# 03_-_MAIN_BOARD.net
KiCad netlist of a schematic drawn in Altium Designer
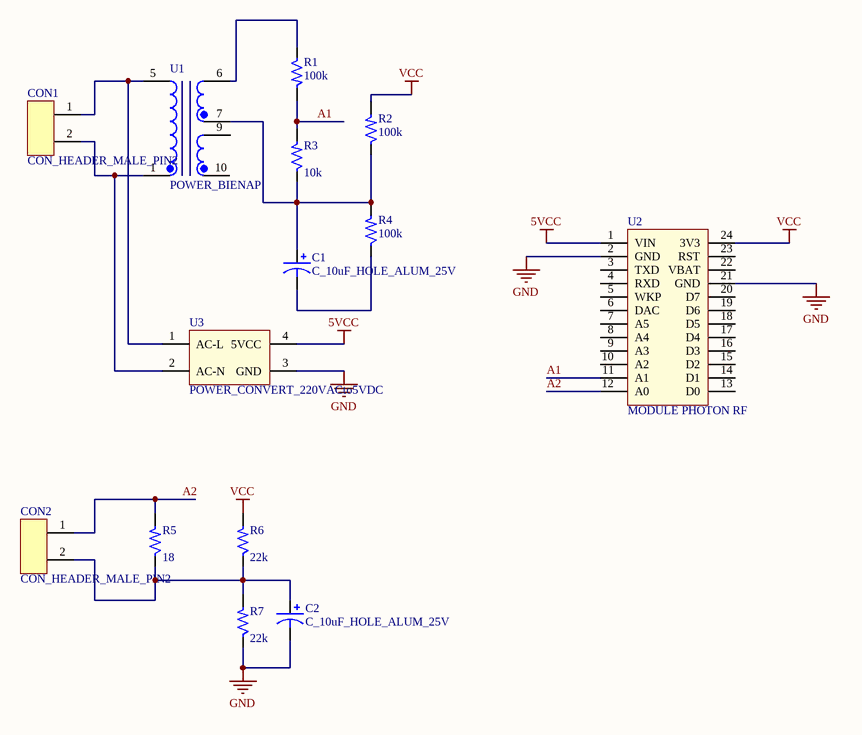
[diagram p0: [03] - MAIN BOARD.SchDoc]

(export (version "E")
  (design (tool "Eeschema 10.0.6"))
  (components
    (comp (ref "C1")
      (value "C_10uF_HOLE_ALUM_25V")
      (footprint "C_10uF_HOLE_5mm")
      (description "CAP ALUM 10uF 20% 25V")
      (fields
        (field (name "MANUFACTURER") "Panasonic Electronic Components")
        (field (name "MANUFACTURER PART NUMBER") "ECE-A1EN100U")
      )
      (libsource (lib "SchematicLib") (part "C_10uF_HOLE_ALUM_25V"))
    )
    (comp (ref "C2")
      (value "C_10uF_HOLE_ALUM_25V")
      (footprint "C_10uF_HOLE_5mm")
      (description "CAP ALUM 10uF 20% 25V")
      (fields
        (field (name "MANUFACTURER") "Panasonic Electronic Components")
        (field (name "MANUFACTURER PART NUMBER") "ECE-A1EN100U")
      )
      (libsource (lib "SchematicLib") (part "C_10uF_HOLE_ALUM_25V"))
    )
    (comp (ref "CON1")
      (value "CON_HEADER_MALE_PIN2")
      (footprint "CON_HEADER_MALE_VAC")
      (description "TERM BLOCK HDR 2POS R/A 5.08MM")
      (fields
        (field (name "MANUFACTURER") "TE Connectivity AMP Connectors")
        (field (name "MANUFACTURER PART NUMBER") "282815-2")
      )
      (libsource (lib "SchematicLib") (part "CON_HEADER_MALE_PIN2"))
    )
    (comp (ref "CON2")
      (value "CON_HEADER_MALE_PIN2")
      (footprint "CON_HEADER_MALE_PIN2")
      (description "TERM BLOCK HDR 2POS R/A 5.08MM")
      (fields
        (field (name "MANUFACTURER") "TE Connectivity AMP Connectors")
        (field (name "MANUFACTURER PART NUMBER") "282815-2")
      )
      (libsource (lib "SchematicLib") (part "CON_HEADER_MALE_PIN2"))
    )
    (comp (ref "R1")
      (value "R_100k_HOLE_0.1%_1W")
      (footprint "R_HOLE_0.25W_0.4")
      (description "RESISTOR METAL FILM 1W 100K OHM")
      (fields
        (field (name "MANUFACTURER") "Vishay Dale")
        (field (name "MANUFACTURER PART NUMBER") "CPF1100K00BHEE6")
        (field (name "RESISTANCE (OHMS)") "100k")
      )
      (libsource (lib "ALTIUM_LIB") (part "R_100k_HOLE_0.1%_1W"))
    )
    (comp (ref "R2")
      (value "R_100k_HOLE_0.1%_1W")
      (footprint "R_HOLE_0.25W_0.4")
      (description "RESISTOR METAL FILM 1W 100K OHM")
      (fields
        (field (name "MANUFACTURER") "Vishay Dale")
        (field (name "MANUFACTURER PART NUMBER") "CPF1100K00BHEE6")
        (field (name "RESISTANCE (OHMS)") "100k")
      )
      (libsource (lib "ALTIUM_LIB") (part "R_100k_HOLE_0.1%_1W"))
    )
    (comp (ref "R3")
      (value "R_10K_HOLE_1%_1W")
      (footprint "R_HOLE_0.25W_0.4")
      (description "RES 10.0K OHM 1W 1% AXIAL")
      (fields
        (field (name "MANUFACTURER") "Vishay Dale")
        (field (name "MANUFACTURER PART NUMBER") "CMF6010K000FKEB")
        (field (name "RESISTANCE (OHMS)") "10k")
      )
      (libsource (lib "ALTIUM_LIB") (part "R_10K_HOLE_1%_1W"))
    )
    (comp (ref "R4")
      (value "R_100k_HOLE_0.1%_1W")
      (footprint "R_HOLE_0.25W_0.4")
      (description "RESISTOR METAL FILM 1W 100K OHM")
      (fields
        (field (name "MANUFACTURER") "Vishay Dale")
        (field (name "MANUFACTURER PART NUMBER") "CPF1100K00BHEE6")
        (field (name "RESISTANCE (OHMS)") "100k")
      )
      (libsource (lib "ALTIUM_LIB") (part "R_100k_HOLE_0.1%_1W"))
    )
    (comp (ref "R5")
      (value "R_18_HOLE_1%_1W")
      (footprint "R_HOLE_0.25W_0.4")
      (description "RES 18 OHM 1W 1% AXIAL")
      (fields
        (field (name "MANUFACTURER") "Vishay Dale")
        (field (name "MANUFACTURER PART NUMBER") "ALSR0118R00FE12")
        (field (name "RESISTANCE (OHMS)") "18")
      )
      (libsource (lib "ALTIUM_LIB") (part "R_18_HOLE_1%_1W"))
    )
    (comp (ref "R6")
      (value "R_22K_HOLE_1%_1/4W")
      (footprint "R_HOLE_0.25W_0.4")
      (description "RES 22K OHM 1/4W 1% AXIAL")
      (fields
        (field (name "MANUFACTURER") "Stackpole Electronics Inc.")
        (field (name "MANUFACTURER PART NUMBER") "RNMF14FTC22K0")
        (field (name "RESISTANCE (OHMS)") "22k")
      )
      (libsource (lib "ALTIUM_LIB") (part "R_22K_HOLE_1%_1/4W"))
    )
    (comp (ref "R7")
      (value "R_22K_HOLE_1%_1/4W")
      (footprint "R_HOLE_0.25W_0.4")
      (description "RES 22K OHM 1/4W 1% AXIAL")
      (fields
        (field (name "MANUFACTURER") "Stackpole Electronics Inc.")
        (field (name "MANUFACTURER PART NUMBER") "RNMF14FTC22K0")
        (field (name "RESISTANCE (OHMS)") "22k")
      )
      (libsource (lib "ALTIUM_LIB") (part "R_22K_HOLE_1%_1/4W"))
    )
    (comp (ref "U1")
      (value "POWER_BIENAP")
      (footprint "POWER_BIEN_AP")
      (libsource (lib "ALTIUM_LIB") (part "POWER_BIENAP"))
    )
    (comp (ref "U2")
      (value "MODULE PHOTON RF")
      (footprint "MODULE PHOTON RF")
      (description "PARTICLE PHOTON")
      (fields
        (field (name "MANUFACTURER") "Seeed Technology Co., Ltd")
        (field (name "MANUFACTURER PART NUMBER") "114990286")
      )
      (libsource (lib "ALTIUM_LIB") (part "MODULE PHOTON RF"))
    )
    (comp (ref "U3")
      (value "POWER_CONVERT_220VACto5VDC")
      (footprint "POWER_CONVERT220VACto5VDC")
      (libsource (lib "SchematicLib") (part "POWER_CONVERT_220VACto5VDC"))
    )
  )
  (nets
    (net (code "1") (name "/A1") (class "Default")
      (node (ref "R1") (pin "2") (pinfunction "2_2") (pintype "passive"))
      (node (ref "R3") (pin "2") (pinfunction "2_2") (pintype "passive"))
      (node (ref "U2") (pin "11") (pinfunction "A1_11") (pintype "passive"))
    )
    (net (code "2") (name "/A2") (class "Default")
      (node (ref "CON2") (pin "1") (pinfunction "SIGN+_1") (pintype "passive"))
      (node (ref "R5") (pin "2") (pinfunction "2_2") (pintype "passive"))
      (node (ref "U2") (pin "12") (pinfunction "A0_12") (pintype "passive"))
    )
    (net (code "3") (name "5VCC") (class "Default")
      (node (ref "U2") (pin "1") (pinfunction "VIN_1") (pintype "passive"))
      (node (ref "U3") (pin "4") (pinfunction "5VCC_4") (pintype "passive"))
    )
    (net (code "4") (name "GND") (class "Default")
      (node (ref "C2") (pin "2") (pinfunction "2_2") (pintype "passive"))
      (node (ref "R7") (pin "1") (pinfunction "1_1") (pintype "passive"))
      (node (ref "U2") (pin "2") (pinfunction "GND_2") (pintype "passive"))
      (node (ref "U2") (pin "21") (pinfunction "GND_21") (pintype "passive"))
      (node (ref "U3") (pin "3") (pinfunction "GND_3") (pintype "passive"))
    )
    (net (code "5") (name "Net-(C1-Pad1)") (class "Default")
      (node (ref "C1") (pin "1") (pinfunction "1_1") (pintype "passive"))
      (node (ref "R2") (pin "1") (pinfunction "1_1") (pintype "passive"))
      (node (ref "R3") (pin "1") (pinfunction "1_1") (pintype "passive"))
      (node (ref "R4") (pin "2") (pinfunction "2_2") (pintype "passive"))
      (node (ref "U1") (pin "7") (pinfunction "7_7") (pintype "passive"))
    )
    (net (code "6") (name "Net-(C1-Pad2)") (class "Default")
      (node (ref "C1") (pin "2") (pinfunction "2_2") (pintype "passive"))
      (node (ref "R4") (pin "1") (pinfunction "1_1") (pintype "passive"))
    )
    (net (code "7") (name "Net-(CON1-SIGN+)") (class "Default")
      (node (ref "CON1") (pin "1") (pinfunction "SIGN+_1") (pintype "passive"))
      (node (ref "U1") (pin "5") (pinfunction "5_5") (pintype "passive"))
      (node (ref "U3") (pin "1") (pinfunction "AC-L_1") (pintype "passive"))
    )
    (net (code "8") (name "Net-(CON1-SIGN-)") (class "Default")
      (node (ref "CON1") (pin "2") (pinfunction "SIGN-_2") (pintype "passive"))
      (node (ref "U1") (pin "1") (pinfunction "1_1") (pintype "passive"))
      (node (ref "U3") (pin "2") (pinfunction "AC-N_2") (pintype "passive"))
    )
    (net (code "9") (name "Net-(CON2-SIGN-)") (class "Default")
      (node (ref "C2") (pin "1") (pinfunction "1_1") (pintype "passive"))
      (node (ref "CON2") (pin "2") (pinfunction "SIGN-_2") (pintype "passive"))
      (node (ref "R5") (pin "1") (pinfunction "1_1") (pintype "passive"))
      (node (ref "R6") (pin "1") (pinfunction "1_1") (pintype "passive"))
      (node (ref "R7") (pin "2") (pinfunction "2_2") (pintype "passive"))
    )
    (net (code "10") (name "Net-(R1-Pad1)") (class "Default")
      (node (ref "R1") (pin "1") (pinfunction "1_1") (pintype "passive"))
      (node (ref "U1") (pin "6") (pinfunction "6_6") (pintype "passive"))
    )
    (net (code "11") (name "VCC") (class "Default")
      (node (ref "R2") (pin "2") (pinfunction "2_2") (pintype "passive"))
      (node (ref "R6") (pin "2") (pinfunction "2_2") (pintype "passive"))
      (node (ref "U2") (pin "24") (pinfunction "3V3_24") (pintype "passive"))
    )
    (net (code "12") (name "unconnected-(U1-Pad9)") (class "Default")
      (node (ref "U1") (pin "9") (pinfunction "9_9") (pintype "passive"))
    )
    (net (code "13") (name "unconnected-(U1-Pad10)") (class "Default")
      (node (ref "U1") (pin "10") (pinfunction "10_10") (pintype "passive"))
    )
    (net (code "14") (name "unconnected-(U2-A2-Pad10)") (class "Default")
      (node (ref "U2") (pin "10") (pinfunction "A2_10") (pintype "passive"))
    )
    (net (code "15") (name "unconnected-(U2-A3-Pad9)") (class "Default")
      (node (ref "U2") (pin "9") (pinfunction "A3_9") (pintype "passive"))
    )
    (net (code "16") (name "unconnected-(U2-A4-Pad8)") (class "Default")
      (node (ref "U2") (pin "8") (pinfunction "A4_8") (pintype "passive"))
    )
    (net (code "17") (name "unconnected-(U2-A5-Pad7)") (class "Default")
      (node (ref "U2") (pin "7") (pinfunction "A5_7") (pintype "passive"))
    )
    (net (code "18") (name "unconnected-(U2-D0-Pad13)") (class "Default")
      (node (ref "U2") (pin "13") (pinfunction "D0_13") (pintype "passive"))
    )
    (net (code "19") (name "unconnected-(U2-D1-Pad14)") (class "Default")
      (node (ref "U2") (pin "14") (pinfunction "D1_14") (pintype "passive"))
    )
    (net (code "20") (name "unconnected-(U2-D2-Pad15)") (class "Default")
      (node (ref "U2") (pin "15") (pinfunction "D2_15") (pintype "passive"))
    )
    (net (code "21") (name "unconnected-(U2-D3-Pad16)") (class "Default")
      (node (ref "U2") (pin "16") (pinfunction "D3_16") (pintype "passive"))
    )
    (net (code "22") (name "unconnected-(U2-D4-Pad17)") (class "Default")
      (node (ref "U2") (pin "17") (pinfunction "D4_17") (pintype "passive"))
    )
    (net (code "23") (name "unconnected-(U2-D5-Pad18)") (class "Default")
      (node (ref "U2") (pin "18") (pinfunction "D5_18") (pintype "passive"))
    )
    (net (code "24") (name "unconnected-(U2-D6-Pad19)") (class "Default")
      (node (ref "U2") (pin "19") (pinfunction "D6_19") (pintype "passive"))
    )
    (net (code "25") (name "unconnected-(U2-D7-Pad20)") (class "Default")
      (node (ref "U2") (pin "20") (pinfunction "D7_20") (pintype "passive"))
    )
    (net (code "26") (name "unconnected-(U2-DAC-Pad6)") (class "Default")
      (node (ref "U2") (pin "6") (pinfunction "DAC_6") (pintype "passive"))
    )
    (net (code "27") (name "unconnected-(U2-RST-Pad23)") (class "Default")
      (node (ref "U2") (pin "23") (pinfunction "RST_23") (pintype "passive"))
    )
    (net (code "28") (name "unconnected-(U2-RXD-Pad4)") (class "Default")
      (node (ref "U2") (pin "4") (pinfunction "RXD_4") (pintype "passive"))
    )
    (net (code "29") (name "unconnected-(U2-TXD-Pad3)") (class "Default")
      (node (ref "U2") (pin "3") (pinfunction "TXD_3") (pintype "passive"))
    )
    (net (code "30") (name "unconnected-(U2-VBAT-Pad22)") (class "Default")
      (node (ref "U2") (pin "22") (pinfunction "VBAT_22") (pintype "passive"))
    )
    (net (code "31") (name "unconnected-(U2-WKP-Pad5)") (class "Default")
      (node (ref "U2") (pin "5") (pinfunction "WKP_5") (pintype "passive"))
    )
  )
)
